# amebot_arduino_leds.net
KiCad netlist of a schematic drawn in EAGLE
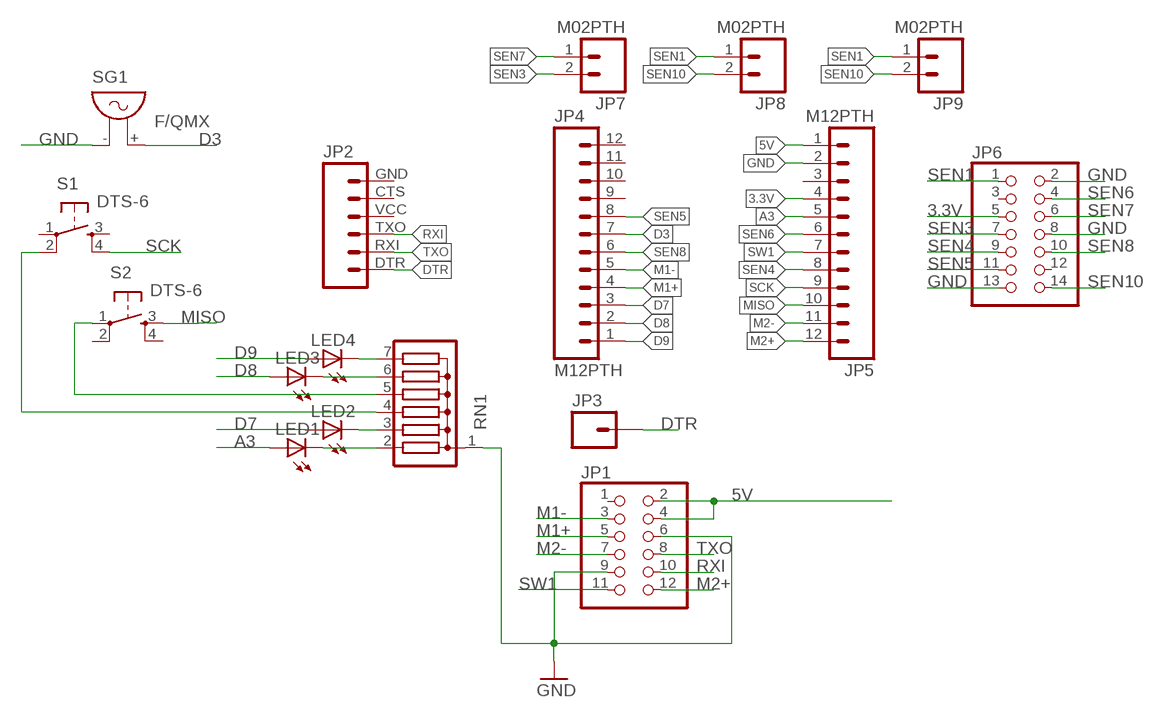
[diagram p0: schematic, sheet 1]

(export (version "E")
  (design (tool "Eeschema 10.0.6"))
  (components
    (comp (ref "JP1")
      (value "PINHD-2X6")
      (footprint "eagle-import:2X06")
      (libsource (lib "eagle-import") (part "PINHD-2X6"))
    )
    (comp (ref "JP2")
      (value "M06SIP")
      (footprint "eagle-import:1X06")
      (libsource (lib "eagle-import") (part "M06SIP"))
    )
    (comp (ref "JP3")
      (value "M01PTH_LONGPAD")
      (footprint "eagle-import:1X01_LONGPAD")
      (libsource (lib "eagle-import") (part "M01PTH_LONGPAD"))
    )
    (comp (ref "JP4")
      (value "M12PTH")
      (footprint "eagle-import:1X12")
      (libsource (lib "eagle-import") (part "M12PTH"))
    )
    (comp (ref "JP5")
      (value "M12PTH")
      (footprint "eagle-import:1X12")
      (libsource (lib "eagle-import") (part "M12PTH"))
    )
    (comp (ref "JP6")
      (value "PINHD-2X7")
      (footprint "eagle-import:2X07")
      (libsource (lib "eagle-import") (part "PINHD-2X7"))
    )
    (comp (ref "JP7")
      (value "M02PTH")
      (footprint "eagle-import:1X02")
      (libsource (lib "eagle-import") (part "M02PTH"))
    )
    (comp (ref "JP8")
      (value "M02PTH")
      (footprint "eagle-import:1X02")
      (libsource (lib "eagle-import") (part "M02PTH"))
    )
    (comp (ref "JP9")
      (value "M02PTH")
      (footprint "eagle-import:1X02")
      (libsource (lib "eagle-import") (part "M02PTH"))
    )
    (comp (ref "LED1")
      (value "LED3MM")
      (footprint "eagle-import:LED3MM")
      (libsource (lib "eagle-import") (part "LED3MM"))
    )
    (comp (ref "LED2")
      (value "LED3MM")
      (footprint "eagle-import:LED3MM")
      (libsource (lib "eagle-import") (part "LED3MM"))
    )
    (comp (ref "LED3")
      (value "LED3MM")
      (footprint "eagle-import:LED3MM")
      (libsource (lib "eagle-import") (part "LED3MM"))
    )
    (comp (ref "LED4")
      (value "LED3MM")
      (footprint "eagle-import:LED3MM")
      (libsource (lib "eagle-import") (part "LED3MM"))
    )
    (comp (ref "RN1")
      (value "G06R")
      (footprint "eagle-import:SIL7")
      (libsource (lib "eagle-import") (part "G06R"))
    )
    (comp (ref "S1")
      (value "DTS-6")
      (footprint "eagle-import:DTS-6")
      (libsource (lib "eagle-import") (part "DTS-6"))
    )
    (comp (ref "S2")
      (value "DTS-6")
      (footprint "eagle-import:DTS-6")
      (libsource (lib "eagle-import") (part "DTS-6"))
    )
    (comp (ref "SG1")
      (value "F/QMX")
      (footprint "eagle-import:F_QMX")
      (libsource (lib "eagle-import") (part "F/QMX"))
    )
  )
  (nets
    (net (code "1") (name "3.3V") (class "Default")
      (node (ref "JP5") (pin "4") (pinfunction "4_4") (pintype "passive"))
      (node (ref "JP6") (pin "5") (pinfunction "5_5") (pintype "passive"))
    )
    (net (code "2") (name "5V") (class "Default")
      (node (ref "JP1") (pin "2") (pinfunction "2_2") (pintype "passive"))
      (node (ref "JP1") (pin "4") (pinfunction "4_4") (pintype "passive"))
      (node (ref "JP5") (pin "1") (pinfunction "1_1") (pintype "passive"))
    )
    (net (code "3") (name "A3") (class "Default")
      (node (ref "JP5") (pin "5") (pinfunction "5_5") (pintype "passive"))
      (node (ref "LED1") (pin "A") (pinfunction "A_A") (pintype "passive"))
    )
    (net (code "4") (name "D3") (class "Default")
      (node (ref "JP4") (pin "7") (pinfunction "7_7") (pintype "passive"))
      (node (ref "SG1") (pin "+") (pinfunction "2_+") (pintype "passive"))
    )
    (net (code "5") (name "D7") (class "Default")
      (node (ref "JP4") (pin "3") (pinfunction "3_3") (pintype "passive"))
      (node (ref "LED2") (pin "A") (pinfunction "A_A") (pintype "passive"))
    )
    (net (code "6") (name "D8") (class "Default")
      (node (ref "JP4") (pin "2") (pinfunction "2_2") (pintype "passive"))
      (node (ref "LED3") (pin "A") (pinfunction "A_A") (pintype "passive"))
    )
    (net (code "7") (name "D9") (class "Default")
      (node (ref "JP4") (pin "1") (pinfunction "1_1") (pintype "passive"))
      (node (ref "LED4") (pin "A") (pinfunction "A_A") (pintype "passive"))
    )
    (net (code "8") (name "DTR") (class "Default")
      (node (ref "JP2") (pin "DTR") (pinfunction "1_DTR") (pintype "passive"))
      (node (ref "JP3") (pin "1") (pinfunction "1_1") (pintype "passive"))
    )
    (net (code "9") (name "GND") (class "Default")
      (node (ref "JP1") (pin "6") (pinfunction "6_6") (pintype "passive"))
      (node (ref "JP1") (pin "9") (pinfunction "9_9") (pintype "passive"))
      (node (ref "JP5") (pin "2") (pinfunction "2_2") (pintype "passive"))
      (node (ref "JP6") (pin "13") (pinfunction "13_13") (pintype "passive"))
      (node (ref "JP6") (pin "2") (pinfunction "2_2") (pintype "passive"))
      (node (ref "JP6") (pin "8") (pinfunction "8_8") (pintype "passive"))
      (node (ref "RN1") (pin "1") (pinfunction "1_1") (pintype "passive"))
      (node (ref "SG1") (pin "-") (pinfunction "1_-") (pintype "passive"))
    )
    (net (code "10") (name "M1+") (class "Default")
      (node (ref "JP1") (pin "5") (pinfunction "5_5") (pintype "passive"))
      (node (ref "JP4") (pin "4") (pinfunction "4_4") (pintype "passive"))
    )
    (net (code "11") (name "M1-") (class "Default")
      (node (ref "JP1") (pin "3") (pinfunction "3_3") (pintype "passive"))
      (node (ref "JP4") (pin "5") (pinfunction "5_5") (pintype "passive"))
    )
    (net (code "12") (name "M2+") (class "Default")
      (node (ref "JP1") (pin "12") (pinfunction "12_12") (pintype "passive"))
      (node (ref "JP5") (pin "12") (pinfunction "12_12") (pintype "passive"))
    )
    (net (code "13") (name "M2-") (class "Default")
      (node (ref "JP1") (pin "7") (pinfunction "7_7") (pintype "passive"))
      (node (ref "JP5") (pin "11") (pinfunction "11_11") (pintype "passive"))
    )
    (net (code "14") (name "MISO") (class "Default")
      (node (ref "JP5") (pin "10") (pinfunction "10_10") (pintype "passive"))
      (node (ref "S2") (pin "3") (pinfunction "3_3") (pintype "passive"))
    )
    (net (code "15") (name "Net-(LED1-C)") (class "Default")
      (node (ref "LED1") (pin "K") (pinfunction "C_K") (pintype "passive"))
      (node (ref "RN1") (pin "2") (pinfunction "2_2") (pintype "passive"))
    )
    (net (code "16") (name "Net-(LED2-C)") (class "Default")
      (node (ref "LED2") (pin "K") (pinfunction "C_K") (pintype "passive"))
      (node (ref "RN1") (pin "3") (pinfunction "3_3") (pintype "passive"))
    )
    (net (code "17") (name "Net-(LED3-C)") (class "Default")
      (node (ref "LED3") (pin "K") (pinfunction "C_K") (pintype "passive"))
      (node (ref "RN1") (pin "6") (pinfunction "6_6") (pintype "passive"))
    )
    (net (code "18") (name "Net-(LED4-C)") (class "Default")
      (node (ref "LED4") (pin "K") (pinfunction "C_K") (pintype "passive"))
      (node (ref "RN1") (pin "7") (pinfunction "7_7") (pintype "passive"))
    )
    (net (code "19") (name "Net-(RN1-Pad4)") (class "Default")
      (node (ref "RN1") (pin "4") (pinfunction "4_4") (pintype "passive"))
      (node (ref "S1") (pin "2") (pinfunction "2_2") (pintype "passive"))
    )
    (net (code "20") (name "Net-(RN1-Pad5)") (class "Default")
      (node (ref "RN1") (pin "5") (pinfunction "5_5") (pintype "passive"))
      (node (ref "S2") (pin "1") (pinfunction "1_1") (pintype "passive"))
    )
    (net (code "21") (name "RXI") (class "Default")
      (node (ref "JP1") (pin "10") (pinfunction "10_10") (pintype "passive"))
      (node (ref "JP2") (pin "TXO") (pinfunction "3_TXO") (pintype "passive"))
    )
    (net (code "22") (name "SCK") (class "Default")
      (node (ref "JP5") (pin "9") (pinfunction "9_9") (pintype "passive"))
      (node (ref "S1") (pin "4") (pinfunction "4_4") (pintype "passive"))
    )
    (net (code "23") (name "SEN1") (class "Default")
      (node (ref "JP6") (pin "1") (pinfunction "1_1") (pintype "passive"))
      (node (ref "JP8") (pin "1") (pinfunction "1_1") (pintype "passive"))
      (node (ref "JP9") (pin "1") (pinfunction "1_1") (pintype "passive"))
    )
    (net (code "24") (name "SEN3") (class "Default")
      (node (ref "JP6") (pin "7") (pinfunction "7_7") (pintype "passive"))
      (node (ref "JP7") (pin "2") (pinfunction "2_2") (pintype "passive"))
    )
    (net (code "25") (name "SEN4") (class "Default")
      (node (ref "JP5") (pin "8") (pinfunction "8_8") (pintype "passive"))
      (node (ref "JP6") (pin "9") (pinfunction "9_9") (pintype "passive"))
    )
    (net (code "26") (name "SEN5") (class "Default")
      (node (ref "JP4") (pin "8") (pinfunction "8_8") (pintype "passive"))
      (node (ref "JP6") (pin "11") (pinfunction "11_11") (pintype "passive"))
    )
    (net (code "27") (name "SEN6") (class "Default")
      (node (ref "JP5") (pin "6") (pinfunction "6_6") (pintype "passive"))
      (node (ref "JP6") (pin "4") (pinfunction "4_4") (pintype "passive"))
    )
    (net (code "28") (name "SEN7") (class "Default")
      (node (ref "JP6") (pin "6") (pinfunction "6_6") (pintype "passive"))
      (node (ref "JP7") (pin "1") (pinfunction "1_1") (pintype "passive"))
    )
    (net (code "29") (name "SEN8") (class "Default")
      (node (ref "JP4") (pin "6") (pinfunction "6_6") (pintype "passive"))
      (node (ref "JP6") (pin "10") (pinfunction "10_10") (pintype "passive"))
    )
    (net (code "30") (name "SEN10") (class "Default")
      (node (ref "JP6") (pin "14") (pinfunction "14_14") (pintype "passive"))
      (node (ref "JP8") (pin "2") (pinfunction "2_2") (pintype "passive"))
      (node (ref "JP9") (pin "2") (pinfunction "2_2") (pintype "passive"))
    )
    (net (code "31") (name "SW1") (class "Default")
      (node (ref "JP1") (pin "11") (pinfunction "11_11") (pintype "passive"))
      (node (ref "JP5") (pin "7") (pinfunction "7_7") (pintype "passive"))
    )
    (net (code "32") (name "TXO") (class "Default")
      (node (ref "JP1") (pin "8") (pinfunction "8_8") (pintype "passive"))
      (node (ref "JP2") (pin "RXI") (pinfunction "2_RXI") (pintype "passive"))
    )
    (net (code "33") (name "unconnected-(JP1-Pad1)") (class "Default")
      (node (ref "JP1") (pin "1") (pinfunction "1_1") (pintype "passive"))
    )
    (net (code "34") (name "unconnected-(JP2-4-PadVCC)") (class "Default")
      (node (ref "JP2") (pin "VCC") (pinfunction "4_VCC") (pintype "passive"))
    )
    (net (code "35") (name "unconnected-(JP2-5-PadCTS)") (class "Default")
      (node (ref "JP2") (pin "CTS") (pinfunction "5_CTS") (pintype "passive"))
    )
    (net (code "36") (name "unconnected-(JP2-6-PadGND)") (class "Default")
      (node (ref "JP2") (pin "GND") (pinfunction "6_GND") (pintype "passive"))
    )
    (net (code "37") (name "unconnected-(JP4-Pad9)") (class "Default")
      (node (ref "JP4") (pin "9") (pinfunction "9_9") (pintype "passive"))
    )
    (net (code "38") (name "unconnected-(JP4-Pad10)") (class "Default")
      (node (ref "JP4") (pin "10") (pinfunction "10_10") (pintype "passive"))
    )
    (net (code "39") (name "unconnected-(JP4-Pad11)") (class "Default")
      (node (ref "JP4") (pin "11") (pinfunction "11_11") (pintype "passive"))
    )
    (net (code "40") (name "unconnected-(JP4-Pad12)") (class "Default")
      (node (ref "JP4") (pin "12") (pinfunction "12_12") (pintype "passive"))
    )
    (net (code "41") (name "unconnected-(JP5-Pad3)") (class "Default")
      (node (ref "JP5") (pin "3") (pinfunction "3_3") (pintype "passive"))
    )
    (net (code "42") (name "unconnected-(JP6-Pad3)") (class "Default")
      (node (ref "JP6") (pin "3") (pinfunction "3_3") (pintype "passive"))
    )
    (net (code "43") (name "unconnected-(JP6-Pad12)") (class "Default")
      (node (ref "JP6") (pin "12") (pinfunction "12_12") (pintype "passive"))
    )
    (net (code "44") (name "unconnected-(S1-Pad1)") (class "Default")
      (node (ref "S1") (pin "1") (pinfunction "1_1") (pintype "passive"))
    )
    (net (code "45") (name "unconnected-(S1-Pad3)") (class "Default")
      (node (ref "S1") (pin "3") (pinfunction "3_3") (pintype "passive"))
    )
    (net (code "46") (name "unconnected-(S2-Pad2)") (class "Default")
      (node (ref "S2") (pin "2") (pinfunction "2_2") (pintype "passive"))
    )
    (net (code "47") (name "unconnected-(S2-Pad4)") (class "Default")
      (node (ref "S2") (pin "4") (pinfunction "4_4") (pintype "passive"))
    )
  )
)
